# question_4.net
KiCad netlist of a schematic drawn in EAGLE
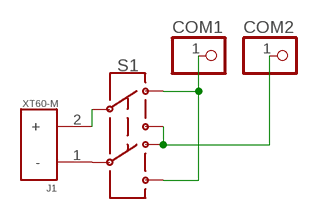
[diagram p0: schematic, sheet 1]

(export (version "E")
  (design (tool "Eeschema 10.0.6"))
  (components
    (comp (ref "COM1")
      (value "PINHD-1X1")
      (footprint "eagle-import:1X01")
      (libsource (lib "eagle-import") (part "PINHD-1X1"))
    )
    (comp (ref "COM2")
      (value "PINHD-1X1")
      (footprint "eagle-import:1X01")
      (libsource (lib "eagle-import") (part "PINHD-1X1"))
    )
    (comp (ref "J1")
      (value "XT60-M")
      (footprint "eagle-import:AMASS_XT60-M")
      (fields (field (name "MF") "AMASS"))
      (libsource (lib "eagle-import") (part "XT60-M"))
    )
    (comp (ref "S1")
      (value "SWITCH-DPDT-SMD-AYZ0202")
      (footprint "eagle-import:SWITCH_DPDT_SMD_AYZ0202")
      (libsource (lib "eagle-import") (part "SWITCH-DPDT-SMD-AYZ0202"))
    )
  )
  (nets
    (net (code "1") (name "Net-(COM1-Pad1)") (class "Default")
      (node (ref "COM1") (pin "1") (pinfunction "1_1") (pintype "passive"))
      (node (ref "S1") (pin "1") (pinfunction "1_1") (pintype "bidirectional"))
      (node (ref "S1") (pin "6") (pinfunction "6_6") (pintype "bidirectional"))
    )
    (net (code "2") (name "Net-(COM2-Pad1)") (class "Default")
      (node (ref "COM2") (pin "1") (pinfunction "1_1") (pintype "passive"))
      (node (ref "S1") (pin "3") (pinfunction "3_3") (pintype "bidirectional"))
      (node (ref "S1") (pin "4") (pinfunction "4_4") (pintype "bidirectional"))
    )
    (net (code "3") (name "Net-(J1-+)") (class "Default")
      (node (ref "J1") (pin "2") (pinfunction "+_2") (pintype "passive"))
      (node (ref "S1") (pin "2") (pinfunction "2_2") (pintype "bidirectional"))
    )
    (net (code "4") (name "Net-(J1--)") (class "Default")
      (node (ref "J1") (pin "1") (pinfunction "-_1") (pintype "passive"))
      (node (ref "S1") (pin "5") (pinfunction "5_5") (pintype "bidirectional"))
    )
  )
)
